# Eagle_Button.net
KiCad netlist of a schematic drawn in EAGLE
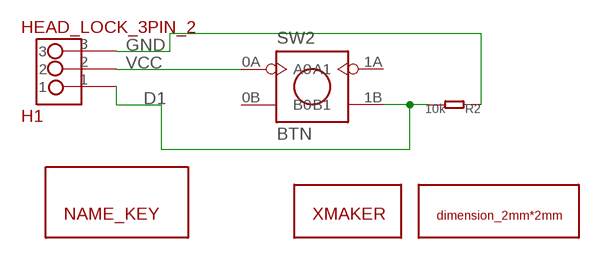
[diagram p0: schematic, sheet 1]

(export (version "E")
  (design (tool "Eeschema 10.0.6"))
  (components
    (comp (ref "H1")
      (value "HEAD_LOCK_3PIN_2")
      (footprint "eagle-import:HEAD_LOCK_3PIN_2")
      (libsource (lib "eagle-import") (part "HEAD_LOCK_3PIN_2"))
    )
    (comp (ref "R2")
      (value "10k")
      (footprint "eagle-import:0603")
      (libsource (lib "eagle-import") (part "005-R0603"))
    )
    (comp (ref "SW2")
      (value "BTN")
      (footprint "eagle-import:BTN_8X8")
      (libsource (lib "eagle-import") (part "BTN"))
    )
    (comp (ref "U$1")
      (value "XMAKERLOGO")
      (footprint "eagle-import:XMAKERLOGO")
      (libsource (lib "eagle-import") (part "XMAKERLOGO"))
    )
    (comp (ref "U$3")
      (value "NAME_KEY")
      (footprint "eagle-import:NAME_KEY")
      (libsource (lib "eagle-import") (part "NAME_KEY"))
    )
    (comp (ref "U$4")
      (value "DIMENSION_2MM2MM")
      (footprint "eagle-import:DIMENSION_2MM_2MM")
      (libsource (lib "eagle-import") (part "DIMENSION_2MM2MM"))
    )
  )
  (nets
    (net (code "1") (name "/D1") (class "Default")
      (node (ref "H1") (pin "1") (pinfunction "1_1") (pintype "passive"))
      (node (ref "R2") (pin "2") (pinfunction "2_2") (pintype "passive"))
      (node (ref "SW2") (pin "1B") (pinfunction "B1_1B") (pintype "bidirectional"))
    )
    (net (code "2") (name "/GND") (class "Default")
      (node (ref "H1") (pin "3") (pinfunction "3_3") (pintype "passive"))
      (node (ref "R2") (pin "1") (pinfunction "1_1") (pintype "passive"))
    )
    (net (code "3") (name "/VCC") (class "Default")
      (node (ref "H1") (pin "2") (pinfunction "2_2") (pintype "passive"))
      (node (ref "SW2") (pin "0A") (pinfunction "A0_0A") (pintype "bidirectional"))
    )
    (net (code "4") (name "unconnected-(SW2-A1-Pad1A)") (class "Default")
      (node (ref "SW2") (pin "1A") (pinfunction "A1_1A") (pintype "bidirectional"))
    )
    (net (code "5") (name "unconnected-(SW2-B0-Pad0B)") (class "Default")
      (node (ref "SW2") (pin "0B") (pinfunction "B0_0B") (pintype "bidirectional"))
    )
  )
)
